# Power.net
KiCad netlist of a schematic drawn in Altium Designer
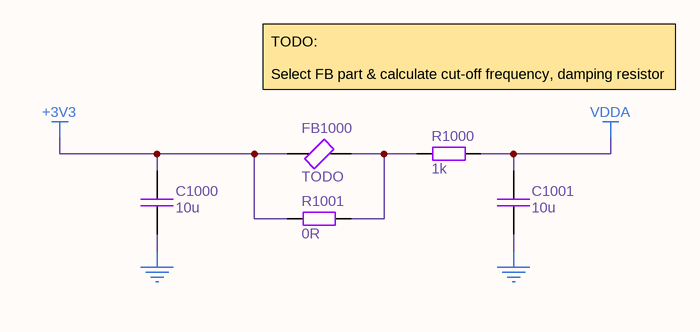
[diagram p0: Power.SchDoc]

(export (version "E")
  (design (tool "Eeschema 10.0.6"))
  (components
    (comp (ref "C1000")
      (value "10u")
      (footprint "CC1206KKX7R8BB106_SMT_1206")
      (description "1206 SMT 10u 25V X7R ceramic capacitor")
      (fields
        (field (name "MANUFACTURER") "YAGEO")
        (field (name "MANUFACTURER PART NUMBER") "CC1206KKX7R8BB106")
      )
      (libsource (lib "algovision") (part "CC1206KKX7R8BB106_SMT_1206"))
    )
    (comp (ref "C1001")
      (value "10u")
      (footprint "CC1206KKX7R8BB106_SMT_1206")
      (description "1206 SMT 10u 25V X7R ceramic capacitor")
      (fields
        (field (name "MANUFACTURER") "YAGEO")
        (field (name "MANUFACTURER PART NUMBER") "CC1206KKX7R8BB106")
      )
      (libsource (lib "algovision") (part "CC1206KKX7R8BB106_SMT_1206"))
    )
    (comp (ref "FB1000")
      (value "TODO")
      (description "TODO FERRITE BEAD")
      (libsource (lib "algovision") (part "FERRITE"))
    )
    (comp (ref "R1000")
      (value "1k")
      (footprint "RC0402FR-071KL_SMT_0402")
      (description "0402 SMT 1k chip resistor")
      (fields
        (field (name "MANUFACTURER") "YAGEO")
        (field (name "MANUFACTURER PART NUMBER") "RC0402FR-071KL")
      )
      (libsource (lib "algovision") (part "RC0402FR-071KL_SMT_0402"))
    )
    (comp (ref "R1001")
      (value "0R")
      (footprint "RC0402JR-070RL_SMT_0402")
      (description "0402 SMT 0R jumper")
      (fields
        (field (name "MANUFACTURER") "YAGEO")
        (field (name "MANUFACTURER PART NUMBER") "RC0402JR-070RL")
      )
      (libsource (lib "algovision") (part "RC0402JR-070RL_SMT_0402"))
    )
  )
  (nets
    (net (code "1") (name "+3V3") (class "Default")
      (node (ref "C1000") (pin "2") (pinfunction "2_2") (pintype "passive"))
      (node (ref "FB1000") (pin "1") (pinfunction "1_1") (pintype "passive"))
      (node (ref "R1001") (pin "1") (pinfunction "1_1") (pintype "passive"))
    )
    (net (code "2") (name "GND") (class "Default")
      (node (ref "C1000") (pin "1") (pinfunction "1_1") (pintype "passive"))
      (node (ref "C1001") (pin "1") (pinfunction "1_1") (pintype "passive"))
    )
    (net (code "3") (name "Net-(FB1000-Pad2)") (class "Default")
      (node (ref "FB1000") (pin "2") (pinfunction "2_2") (pintype "passive"))
      (node (ref "R1000") (pin "1") (pinfunction "1_1") (pintype "passive"))
      (node (ref "R1001") (pin "2") (pinfunction "2_2") (pintype "passive"))
    )
    (net (code "4") (name "VDDA") (class "Default")
      (node (ref "C1001") (pin "2") (pinfunction "2_2") (pintype "passive"))
      (node (ref "R1000") (pin "2") (pinfunction "2_2") (pintype "passive"))
    )
  )
)
